# axiom_beta_plugin_module_TE0714_SATA_v0_.net
KiCad netlist of a schematic drawn in EAGLE
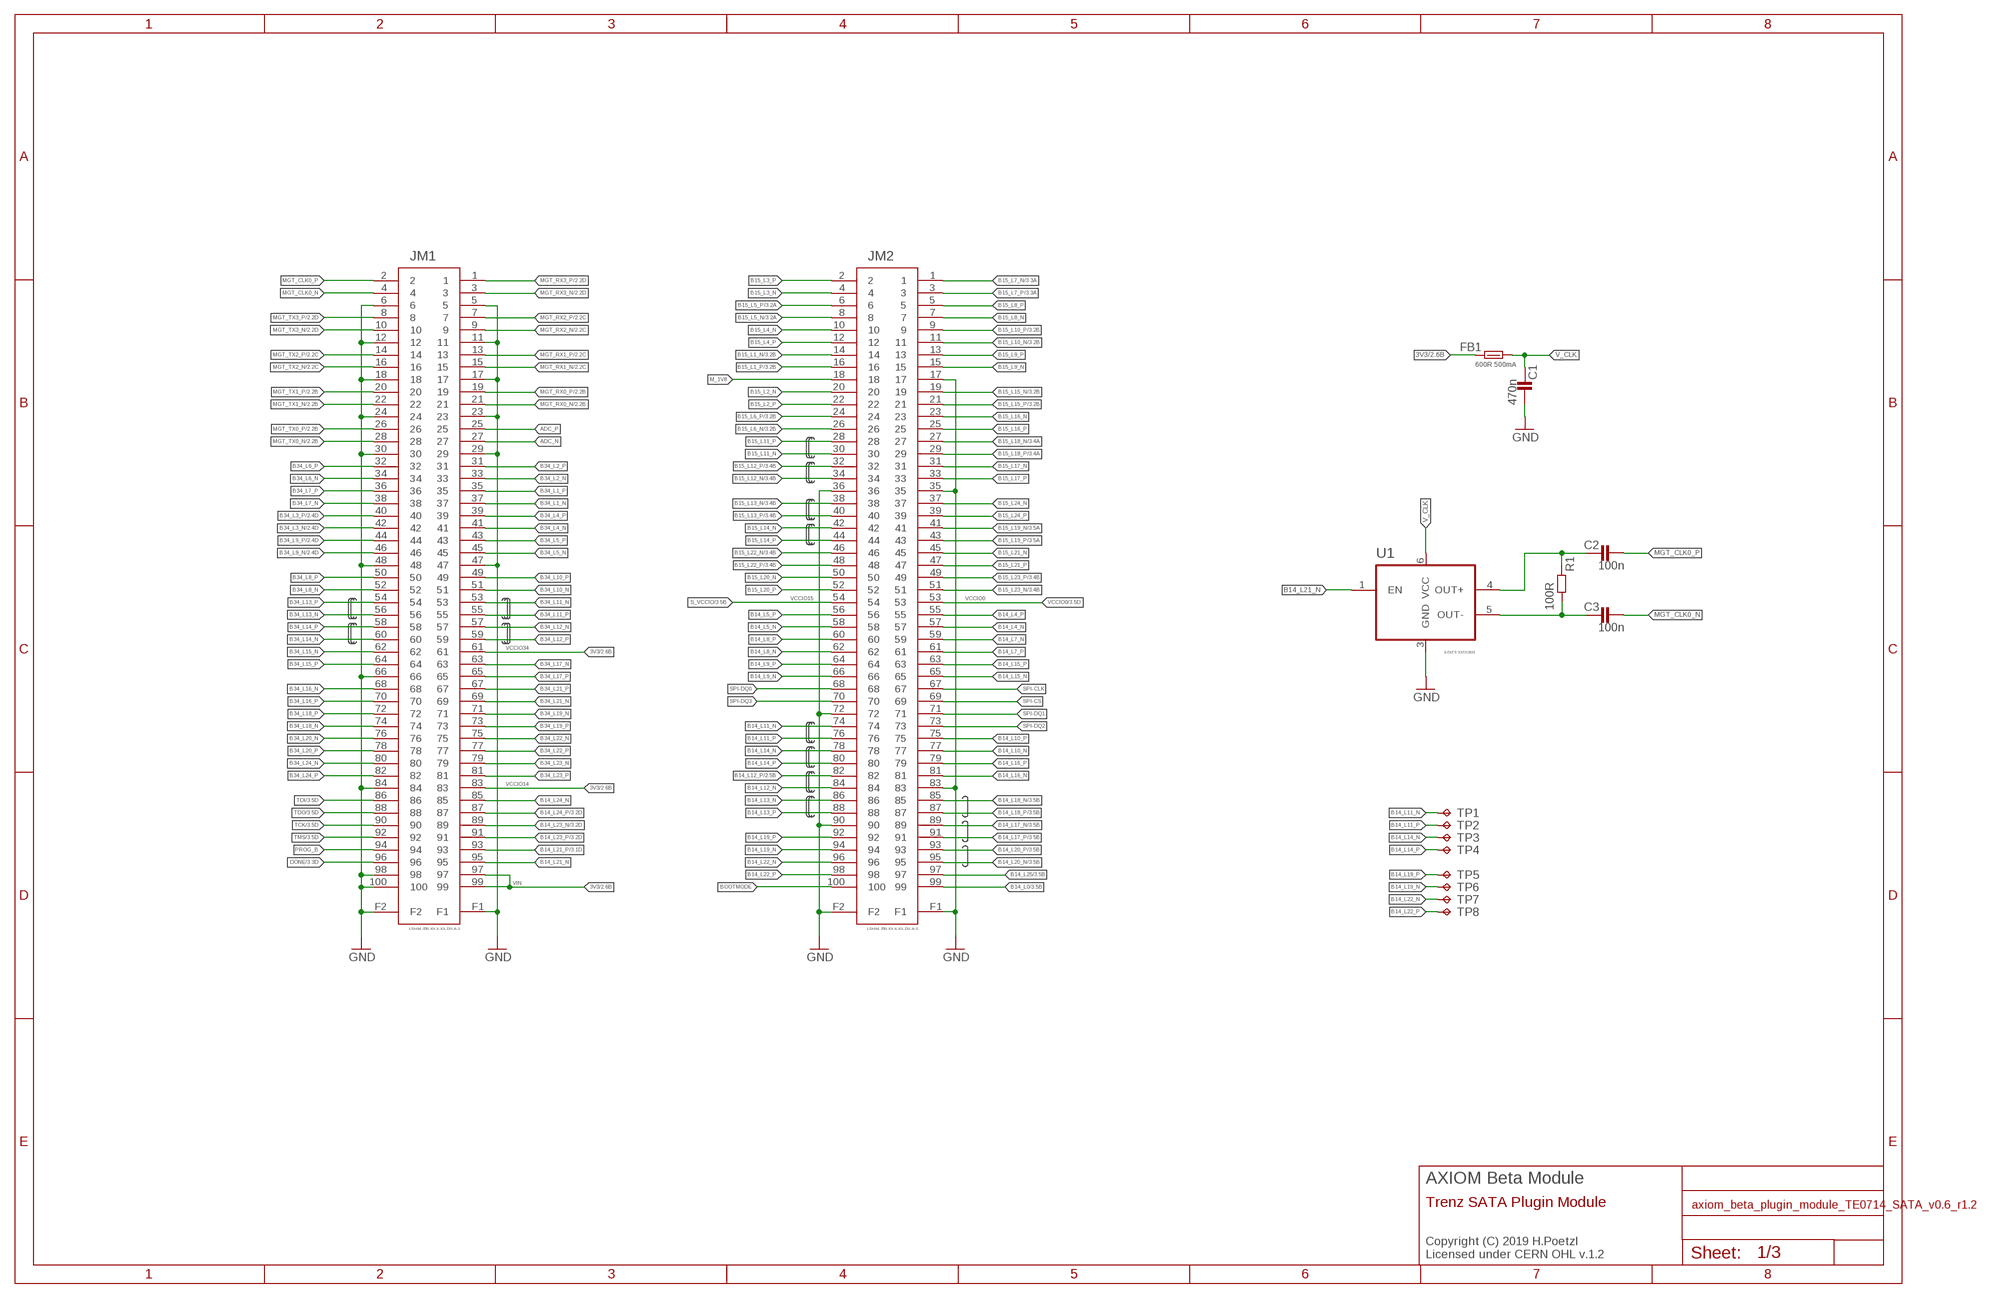
[diagram p0: schematic, sheet 1]
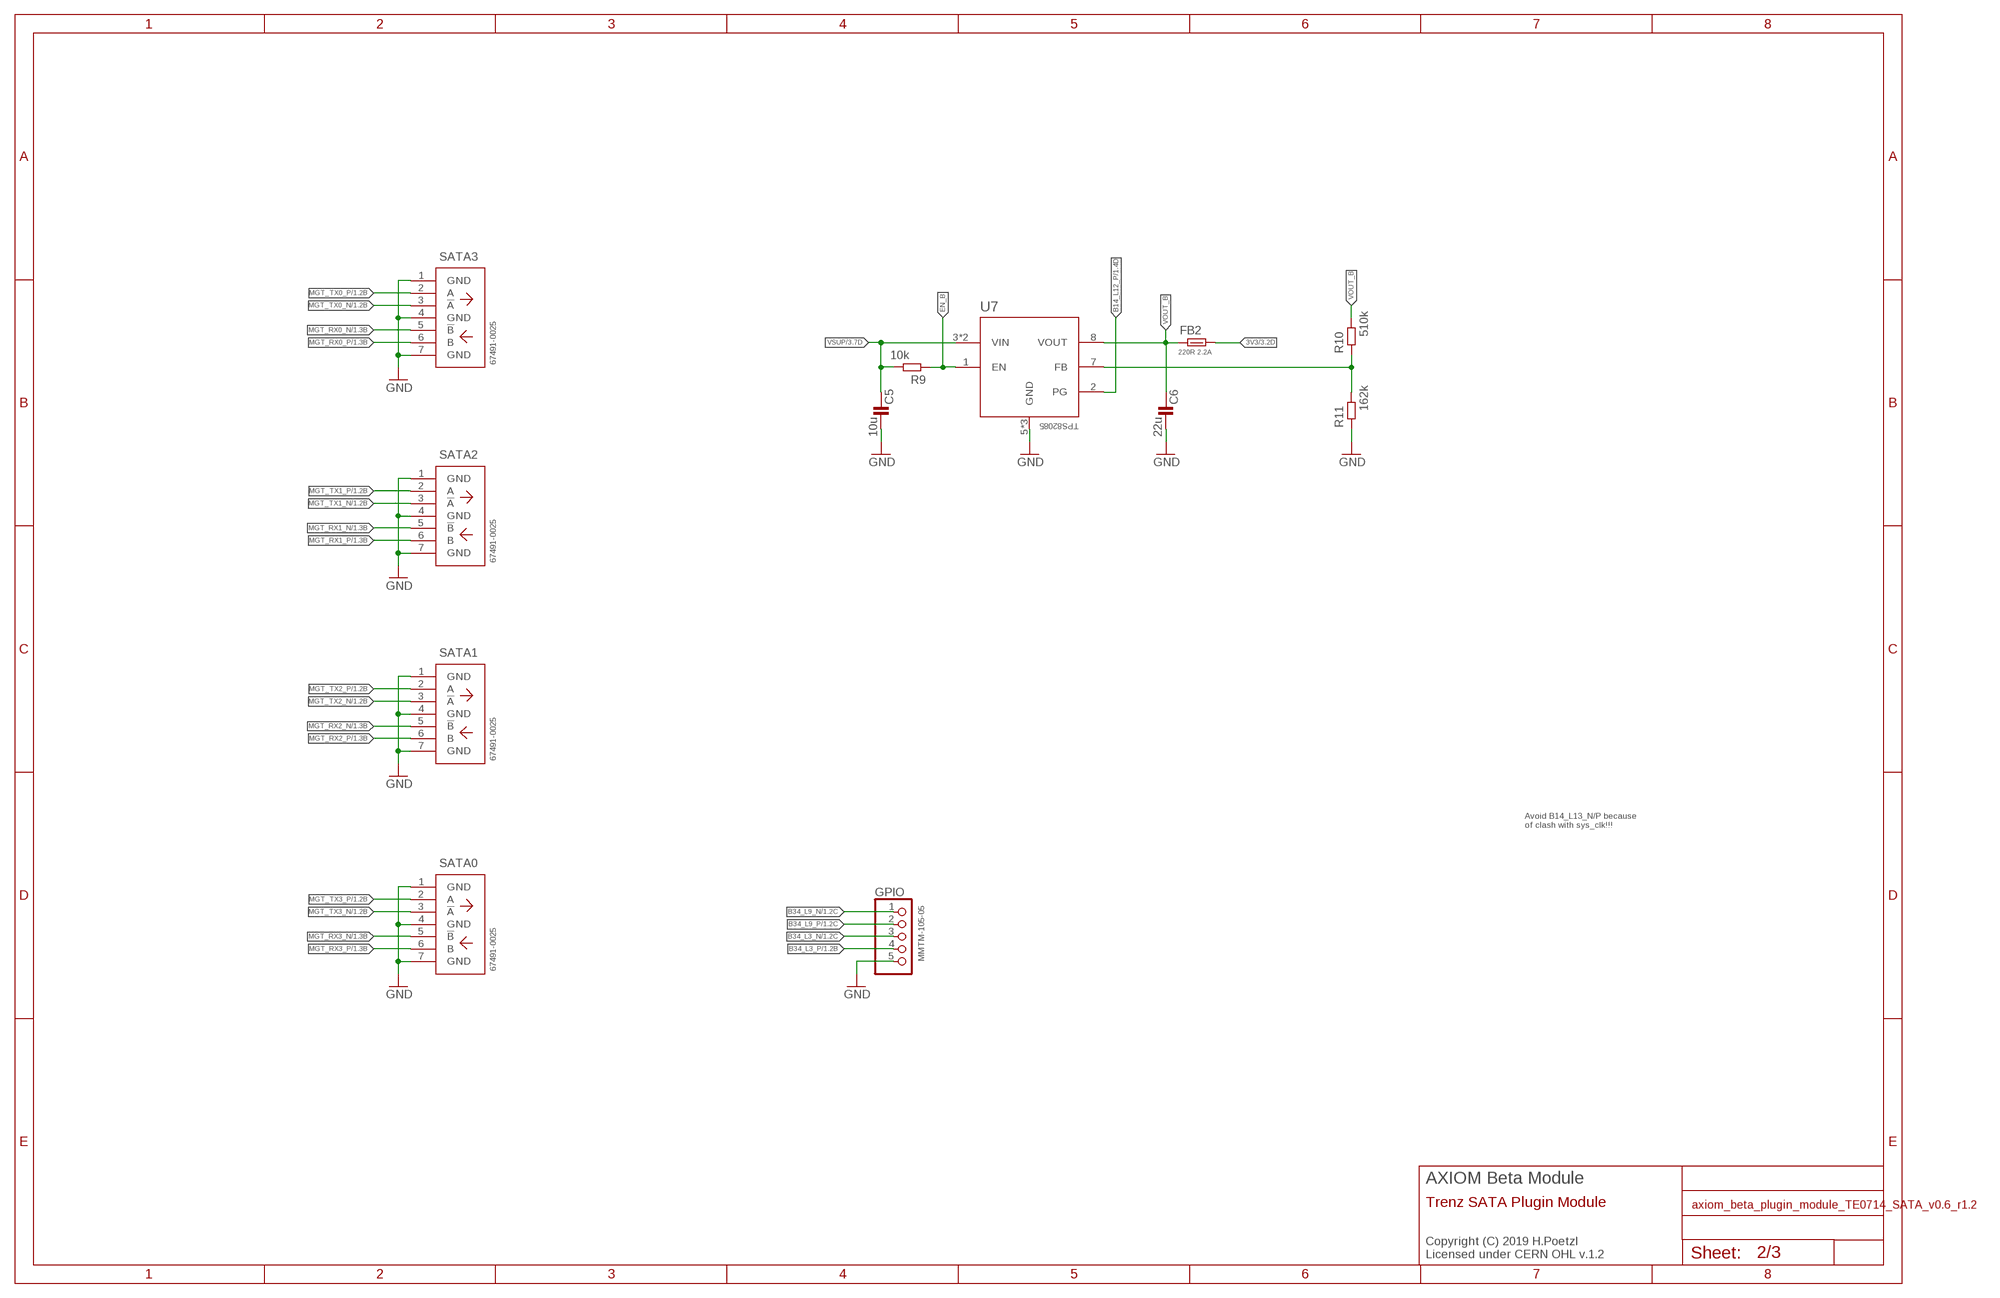
[diagram p1: schematic, sheet 2]
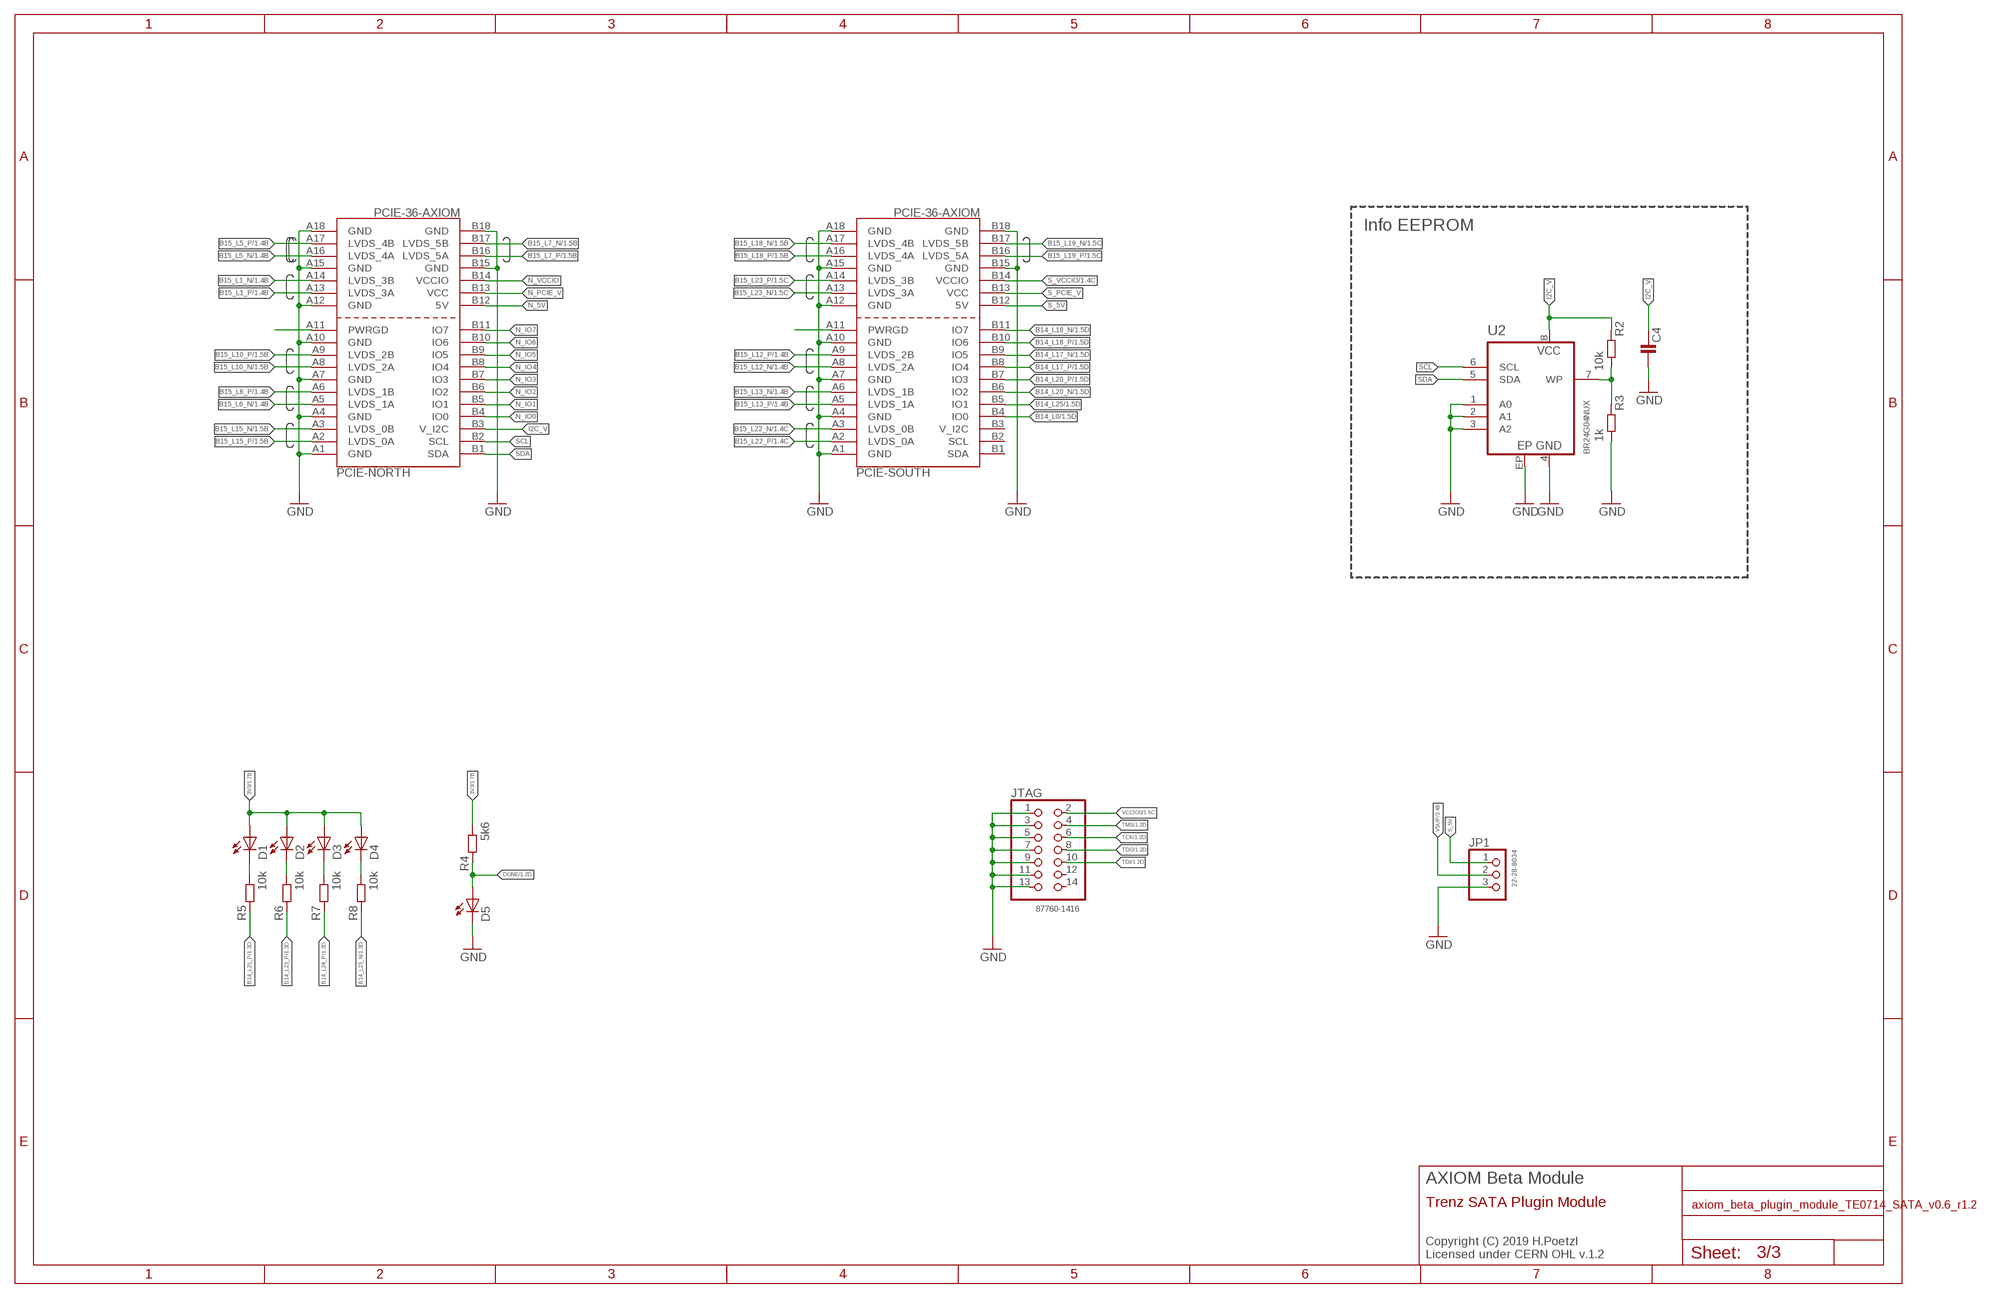
[diagram p2: schematic, sheet 3]

(export (version "E")
  (design (tool "Eeschema 10.0.6"))
  (components
    (comp (ref "C4")
      (value "C0402-B")
      (footprint "eagle-import:0402-B")
      (libsource (lib "eagle-import") (part "C0402-B"))
    )
    (comp (ref "D1")
      (value "LED")
      (footprint "eagle-import:CHIPLED_0603")
      (libsource (lib "eagle-import") (part "LED"))
    )
    (comp (ref "D2")
      (value "LED")
      (footprint "eagle-import:CHIPLED_0603")
      (libsource (lib "eagle-import") (part "LED"))
    )
    (comp (ref "D3")
      (value "LED")
      (footprint "eagle-import:CHIPLED_0603")
      (libsource (lib "eagle-import") (part "LED"))
    )
    (comp (ref "D4")
      (value "LED")
      (footprint "eagle-import:CHIPLED_0603")
      (libsource (lib "eagle-import") (part "LED"))
    )
    (comp (ref "D5")
      (value "LED")
      (footprint "eagle-import:CHIPLED_0603")
      (libsource (lib "eagle-import") (part "LED"))
    )
    (comp (ref "JP1")
      (value "22-28-8034")
      (footprint "eagle-import:1X03_90-S")
      (libsource (lib "eagle-import") (part "PINHD-1X03_2.54-90°-S"))
    )
    (comp (ref "JTAG")
      (value "87760-1416")
      (footprint "eagle-import:2X07M")
      (libsource (lib "eagle-import") (part "PINHD-2X07_2.00"))
    )
    (comp (ref "PCIE-NORTH")
      (value "PCIE-36-AXIOM")
      (footprint "eagle-import:PCIE-36-AXIOM")
      (libsource (lib "eagle-import") (part "PCIE-36-AXIOM"))
    )
    (comp (ref "PCIE-SOUTH")
      (value "PCIE-36-AXIOM")
      (footprint "eagle-import:PCIE-36-AXIOM")
      (libsource (lib "eagle-import") (part "PCIE-36-AXIOM"))
    )
    (comp (ref "R2")
      (value "10k")
      (footprint "eagle-import:0402-B")
      (libsource (lib "eagle-import") (part "R0402-B"))
    )
    (comp (ref "R3")
      (value "1k")
      (footprint "eagle-import:0402-B")
      (libsource (lib "eagle-import") (part "R0402-B"))
    )
    (comp (ref "R4")
      (value "5k6")
      (footprint "eagle-import:0402-C")
      (libsource (lib "eagle-import") (part "R0402-C"))
    )
    (comp (ref "R5")
      (value "10k")
      (footprint "eagle-import:0402-C")
      (libsource (lib "eagle-import") (part "R0402-C"))
    )
    (comp (ref "R6")
      (value "10k")
      (footprint "eagle-import:0402-C")
      (libsource (lib "eagle-import") (part "R0402-C"))
    )
    (comp (ref "R7")
      (value "10k")
      (footprint "eagle-import:0402-C")
      (libsource (lib "eagle-import") (part "R0402-C"))
    )
    (comp (ref "R8")
      (value "10k")
      (footprint "eagle-import:0402-C")
      (libsource (lib "eagle-import") (part "R0402-C"))
    )
    (comp (ref "U2")
      (value "BR24G04NUX")
      (footprint "eagle-import:DFN200X300X100-9N")
      (libsource (lib "eagle-import") (part "BR24G04NUX"))
    )
    (comp (ref "C5")
      (value "10u")
      (footprint "eagle-import:0603-C")
      (libsource (lib "eagle-import") (part "C0603-C"))
    )
    (comp (ref "C6")
      (value "22u")
      (footprint "eagle-import:0603-C")
      (libsource (lib "eagle-import") (part "C0603-C"))
    )
    (comp (ref "FB2")
      (value "220R 2.2A")
      (footprint "eagle-import:0603-C")
      (libsource (lib "eagle-import") (part "FB0603-C"))
    )
    (comp (ref "GPIO")
      (value "MMTM-105-05")
      (footprint "eagle-import:1X05M")
      (libsource (lib "eagle-import") (part "PINHD-1X05_2.00"))
    )
    (comp (ref "R9")
      (value "10k")
      (footprint "eagle-import:0201-C")
      (libsource (lib "eagle-import") (part "R0201-C"))
    )
    (comp (ref "R10")
      (value "510k")
      (footprint "eagle-import:0201-C")
      (libsource (lib "eagle-import") (part "R0201-C"))
    )
    (comp (ref "R11")
      (value "162k")
      (footprint "eagle-import:0201-C")
      (libsource (lib "eagle-import") (part "R0201-C"))
    )
    (comp (ref "SATA0")
      (value "67491-0025")
      (footprint "eagle-import:SATA7-VERT-S")
      (libsource (lib "eagle-import") (part "SATA7-VERT-S"))
    )
    (comp (ref "SATA1")
      (value "67491-0025")
      (footprint "eagle-import:SATA7-VERT-S")
      (libsource (lib "eagle-import") (part "SATA7-VERT-S"))
    )
    (comp (ref "SATA2")
      (value "67491-0025")
      (footprint "eagle-import:SATA7-VERT-S")
      (libsource (lib "eagle-import") (part "SATA7-VERT-S"))
    )
    (comp (ref "SATA3")
      (value "67491-0025")
      (footprint "eagle-import:SATA7-VERT-S")
      (libsource (lib "eagle-import") (part "SATA7-VERT-S"))
    )
    (comp (ref "U7")
      (value "TPS82085")
      (footprint "eagle-import:MICROSIP")
      (libsource (lib "eagle-import") (part "TPS82085"))
    )
    (comp (ref "C1")
      (value "470n")
      (footprint "eagle-import:0402-C")
      (libsource (lib "eagle-import") (part "C0402-C"))
    )
    (comp (ref "C2")
      (value "100n")
      (footprint "eagle-import:0201-C")
      (libsource (lib "eagle-import") (part "C0201-C"))
    )
    (comp (ref "C3")
      (value "100n")
      (footprint "eagle-import:0201-C")
      (libsource (lib "eagle-import") (part "C0201-C"))
    )
    (comp (ref "FB1")
      (value "600R 500mA")
      (footprint "eagle-import:0402-C")
      (libsource (lib "eagle-import") (part "FB0402-C"))
    )
    (comp (ref "JM1")
      (value "LSHM-150-XX.X-XX-DV-A-S")
      (footprint "eagle-import:LSHM-150-XX.X-XX-DV-A-S")
      (libsource (lib "eagle-import") (part "LSHM-150-XX.X-XX-DV-A-S"))
    )
    (comp (ref "JM2")
      (value "LSHM-150-XX.X-XX-DV-A-S")
      (footprint "eagle-import:LSHM-150-XX.X-XX-DV-A-S")
      (libsource (lib "eagle-import") (part "LSHM-150-XX.X-XX-DV-A-S"))
    )
    (comp (ref "R1")
      (value "100R")
      (footprint "eagle-import:0201-C")
      (libsource (lib "eagle-import") (part "R0201-C"))
    )
    (comp (ref "TP1")
      (value "TPTP10R")
      (footprint "eagle-import:TP10R")
      (libsource (lib "eagle-import") (part "TPTP10R"))
    )
    (comp (ref "TP2")
      (value "TPTP10R")
      (footprint "eagle-import:TP10R")
      (libsource (lib "eagle-import") (part "TPTP10R"))
    )
    (comp (ref "TP3")
      (value "TPTP10R")
      (footprint "eagle-import:TP10R")
      (libsource (lib "eagle-import") (part "TPTP10R"))
    )
    (comp (ref "TP4")
      (value "TPTP10R")
      (footprint "eagle-import:TP10R")
      (libsource (lib "eagle-import") (part "TPTP10R"))
    )
    (comp (ref "TP5")
      (value "TPTP10R")
      (footprint "eagle-import:TP10R")
      (libsource (lib "eagle-import") (part "TPTP10R"))
    )
    (comp (ref "TP6")
      (value "TPTP10R")
      (footprint "eagle-import:TP10R")
      (libsource (lib "eagle-import") (part "TPTP10R"))
    )
    (comp (ref "TP7")
      (value "TPTP10R")
      (footprint "eagle-import:TP10R")
      (libsource (lib "eagle-import") (part "TPTP10R"))
    )
    (comp (ref "TP8")
      (value "TPTP10R")
      (footprint "eagle-import:TP10R")
      (libsource (lib "eagle-import") (part "TPTP10R"))
    )
    (comp (ref "U1")
      (value "DSC11XX-3.2X2.5")
      (footprint "eagle-import:3.2X2.5")
      (libsource (lib "eagle-import") (part "DSC11XX-3.2X2.5"))
    )
  )
  (nets
    (net (code "1") (name "3V3") (class "Default")
      (node (ref "D1") (pin "A") (pinfunction "A_A") (pintype "passive"))
      (node (ref "D2") (pin "A") (pinfunction "A_A") (pintype "passive"))
      (node (ref "D3") (pin "A") (pinfunction "A_A") (pintype "passive"))
      (node (ref "D4") (pin "A") (pinfunction "A_A") (pintype "passive"))
      (node (ref "FB1") (pin "1") (pinfunction "1_1") (pintype "passive"))
      (node (ref "FB2") (pin "2") (pinfunction "2_2") (pintype "passive"))
      (node (ref "JM1") (pin "61") (pinfunction "61_61") (pintype "bidirectional"))
      (node (ref "JM1") (pin "83") (pinfunction "83_83") (pintype "bidirectional"))
      (node (ref "JM1") (pin "97") (pinfunction "97_97") (pintype "bidirectional"))
      (node (ref "JM1") (pin "99") (pinfunction "99_99") (pintype "bidirectional"))
      (node (ref "R4") (pin "2") (pinfunction "2_2") (pintype "passive"))
    )
    (net (code "2") (name "ADC_N") (class "Default")
      (node (ref "JM1") (pin "27") (pinfunction "27_27") (pintype "bidirectional"))
    )
    (net (code "3") (name "ADC_P") (class "Default")
      (node (ref "JM1") (pin "25") (pinfunction "25_25") (pintype "bidirectional"))
    )
    (net (code "4") (name "B14_L0") (class "Default")
      (node (ref "JM2") (pin "99") (pinfunction "99_99") (pintype "bidirectional"))
      (node (ref "PCIE-SOUTH") (pin "B4") (pinfunction "IO0_B4") (pintype "passive"))
    )
    (net (code "5") (name "B14_L4_N") (class "Default")
      (node (ref "JM2") (pin "57") (pinfunction "57_57") (pintype "bidirectional"))
    )
    (net (code "6") (name "B14_L4_P") (class "Default")
      (node (ref "JM2") (pin "55") (pinfunction "55_55") (pintype "bidirectional"))
    )
    (net (code "7") (name "B14_L5_N") (class "Default")
      (node (ref "JM2") (pin "58") (pinfunction "58_58") (pintype "bidirectional"))
    )
    (net (code "8") (name "B14_L5_P") (class "Default")
      (node (ref "JM2") (pin "56") (pinfunction "56_56") (pintype "bidirectional"))
    )
    (net (code "9") (name "B14_L7_N") (class "Default")
      (node (ref "JM2") (pin "59") (pinfunction "59_59") (pintype "bidirectional"))
    )
    (net (code "10") (name "B14_L7_P") (class "Default")
      (node (ref "JM2") (pin "61") (pinfunction "61_61") (pintype "bidirectional"))
    )
    (net (code "11") (name "B14_L8_N") (class "Default")
      (node (ref "JM2") (pin "62") (pinfunction "62_62") (pintype "bidirectional"))
    )
    (net (code "12") (name "B14_L8_P") (class "Default")
      (node (ref "JM2") (pin "60") (pinfunction "60_60") (pintype "bidirectional"))
    )
    (net (code "13") (name "B14_L9_N") (class "Default")
      (node (ref "JM2") (pin "66") (pinfunction "66_66") (pintype "bidirectional"))
    )
    (net (code "14") (name "B14_L9_P") (class "Default")
      (node (ref "JM2") (pin "64") (pinfunction "64_64") (pintype "bidirectional"))
    )
    (net (code "15") (name "B14_L10_N") (class "Default")
      (node (ref "JM2") (pin "77") (pinfunction "77_77") (pintype "bidirectional"))
    )
    (net (code "16") (name "B14_L10_P") (class "Default")
      (node (ref "JM2") (pin "75") (pinfunction "75_75") (pintype "bidirectional"))
    )
    (net (code "17") (name "B14_L11_N") (class "Default")
      (node (ref "JM2") (pin "74") (pinfunction "74_74") (pintype "bidirectional"))
      (node (ref "TP1") (pin "TP") (pinfunction "TP_TP") (pintype "input"))
    )
    (net (code "18") (name "B14_L11_P") (class "Default")
      (node (ref "JM2") (pin "76") (pinfunction "76_76") (pintype "bidirectional"))
      (node (ref "TP2") (pin "TP") (pinfunction "TP_TP") (pintype "input"))
    )
    (net (code "19") (name "B14_L12_N") (class "Default")
      (node (ref "JM2") (pin "84") (pinfunction "84_84") (pintype "bidirectional"))
    )
    (net (code "20") (name "B14_L12_P") (class "Default")
      (node (ref "JM2") (pin "82") (pinfunction "82_82") (pintype "bidirectional"))
      (node (ref "U7") (pin "2") (pinfunction "PG_2") (pintype "power_in"))
    )
    (net (code "21") (name "B14_L13_N") (class "Default")
      (node (ref "JM2") (pin "86") (pinfunction "86_86") (pintype "bidirectional"))
    )
    (net (code "22") (name "B14_L13_P") (class "Default")
      (node (ref "JM2") (pin "88") (pinfunction "88_88") (pintype "bidirectional"))
    )
    (net (code "23") (name "B14_L14_N") (class "Default")
      (node (ref "JM2") (pin "78") (pinfunction "78_78") (pintype "bidirectional"))
      (node (ref "TP3") (pin "TP") (pinfunction "TP_TP") (pintype "input"))
    )
    (net (code "24") (name "B14_L14_P") (class "Default")
      (node (ref "JM2") (pin "80") (pinfunction "80_80") (pintype "bidirectional"))
      (node (ref "TP4") (pin "TP") (pinfunction "TP_TP") (pintype "input"))
    )
    (net (code "25") (name "B14_L15_N") (class "Default")
      (node (ref "JM2") (pin "65") (pinfunction "65_65") (pintype "bidirectional"))
    )
    (net (code "26") (name "B14_L15_P") (class "Default")
      (node (ref "JM2") (pin "63") (pinfunction "63_63") (pintype "bidirectional"))
    )
    (net (code "27") (name "B14_L16_N") (class "Default")
      (node (ref "JM2") (pin "81") (pinfunction "81_81") (pintype "bidirectional"))
    )
    (net (code "28") (name "B14_L16_P") (class "Default")
      (node (ref "JM2") (pin "79") (pinfunction "79_79") (pintype "bidirectional"))
    )
    (net (code "29") (name "B14_L17_N") (class "Default")
      (node (ref "JM2") (pin "89") (pinfunction "89_89") (pintype "bidirectional"))
      (node (ref "PCIE-SOUTH") (pin "B9") (pinfunction "IO5_B9") (pintype "passive"))
    )
    (net (code "30") (name "B14_L17_P") (class "Default")
      (node (ref "JM2") (pin "91") (pinfunction "91_91") (pintype "bidirectional"))
      (node (ref "PCIE-SOUTH") (pin "B8") (pinfunction "IO4_B8") (pintype "passive"))
    )
    (net (code "31") (name "B14_L18_N") (class "Default")
      (node (ref "JM2") (pin "85") (pinfunction "85_85") (pintype "bidirectional"))
      (node (ref "PCIE-SOUTH") (pin "B11") (pinfunction "IO7_B11") (pintype "passive"))
    )
    (net (code "32") (name "B14_L18_P") (class "Default")
      (node (ref "JM2") (pin "87") (pinfunction "87_87") (pintype "bidirectional"))
      (node (ref "PCIE-SOUTH") (pin "B10") (pinfunction "IO6_B10") (pintype "passive"))
    )
    (net (code "33") (name "B14_L19_N") (class "Default")
      (node (ref "JM2") (pin "94") (pinfunction "94_94") (pintype "bidirectional"))
      (node (ref "TP6") (pin "TP") (pinfunction "TP_TP") (pintype "input"))
    )
    (net (code "34") (name "B14_L19_P") (class "Default")
      (node (ref "JM2") (pin "92") (pinfunction "92_92") (pintype "bidirectional"))
      (node (ref "TP5") (pin "TP") (pinfunction "TP_TP") (pintype "input"))
    )
    (net (code "35") (name "B14_L20_N") (class "Default")
      (node (ref "JM2") (pin "95") (pinfunction "95_95") (pintype "bidirectional"))
      (node (ref "PCIE-SOUTH") (pin "B6") (pinfunction "IO2_B6") (pintype "passive"))
    )
    (net (code "36") (name "B14_L20_P") (class "Default")
      (node (ref "JM2") (pin "93") (pinfunction "93_93") (pintype "bidirectional"))
      (node (ref "PCIE-SOUTH") (pin "B7") (pinfunction "IO3_B7") (pintype "passive"))
    )
    (net (code "37") (name "B14_L21_N") (class "Default")
      (node (ref "JM1") (pin "95") (pinfunction "95_95") (pintype "bidirectional"))
      (node (ref "U1") (pin "1") (pinfunction "EN_1") (pintype "input"))
    )
    (net (code "38") (name "B14_L21_P") (class "Default")
      (node (ref "JM1") (pin "93") (pinfunction "93_93") (pintype "bidirectional"))
      (node (ref "R5") (pin "1") (pinfunction "1_1") (pintype "passive"))
    )
    (net (code "39") (name "B14_L22_N") (class "Default")
      (node (ref "JM2") (pin "96") (pinfunction "96_96") (pintype "bidirectional"))
      (node (ref "TP7") (pin "TP") (pinfunction "TP_TP") (pintype "input"))
    )
    (net (code "40") (name "B14_L22_P") (class "Default")
      (node (ref "JM2") (pin "98") (pinfunction "98_98") (pintype "bidirectional"))
      (node (ref "TP8") (pin "TP") (pinfunction "TP_TP") (pintype "input"))
    )
    (net (code "41") (name "B14_L23_N") (class "Default")
      (node (ref "JM1") (pin "89") (pinfunction "89_89") (pintype "bidirectional"))
      (node (ref "R8") (pin "1") (pinfunction "1_1") (pintype "passive"))
    )
    (net (code "42") (name "B14_L23_P") (class "Default")
      (node (ref "JM1") (pin "91") (pinfunction "91_91") (pintype "bidirectional"))
      (node (ref "R6") (pin "1") (pinfunction "1_1") (pintype "passive"))
    )
    (net (code "43") (name "B14_L24_N") (class "Default")
      (node (ref "JM1") (pin "85") (pinfunction "85_85") (pintype "bidirectional"))
    )
    (net (code "44") (name "B14_L24_P") (class "Default")
      (node (ref "JM1") (pin "87") (pinfunction "87_87") (pintype "bidirectional"))
      (node (ref "R7") (pin "1") (pinfunction "1_1") (pintype "passive"))
    )
    (net (code "45") (name "B14_L25") (class "Default")
      (node (ref "JM2") (pin "97") (pinfunction "97_97") (pintype "bidirectional"))
      (node (ref "PCIE-SOUTH") (pin "B5") (pinfunction "IO1_B5") (pintype "passive"))
    )
    (net (code "46") (name "B15_L1_N") (class "Default")
      (node (ref "JM2") (pin "14") (pinfunction "14_14") (pintype "bidirectional"))
      (node (ref "PCIE-NORTH") (pin "A14") (pinfunction "LVDS_3B_A14") (pintype "passive"))
    )
    (net (code "47") (name "B15_L1_P") (class "Default")
      (node (ref "JM2") (pin "16") (pinfunction "16_16") (pintype "bidirectional"))
      (node (ref "PCIE-NORTH") (pin "A13") (pinfunction "LVDS_3A_A13") (pintype "passive"))
    )
    (net (code "48") (name "B15_L2_N") (class "Default")
      (node (ref "JM2") (pin "20") (pinfunction "20_20") (pintype "bidirectional"))
    )
    (net (code "49") (name "B15_L2_P") (class "Default")
      (node (ref "JM2") (pin "22") (pinfunction "22_22") (pintype "bidirectional"))
    )
    (net (code "50") (name "B15_L3_N") (class "Default")
      (node (ref "JM2") (pin "4") (pinfunction "4_4") (pintype "bidirectional"))
    )
    (net (code "51") (name "B15_L3_P") (class "Default")
      (node (ref "JM2") (pin "2") (pinfunction "2_2") (pintype "bidirectional"))
    )
    (net (code "52") (name "B15_L4_N") (class "Default")
      (node (ref "JM2") (pin "10") (pinfunction "10_10") (pintype "bidirectional"))
    )
    (net (code "53") (name "B15_L4_P") (class "Default")
      (node (ref "JM2") (pin "12") (pinfunction "12_12") (pintype "bidirectional"))
    )
    (net (code "54") (name "B15_L5_N") (class "Default")
      (node (ref "JM2") (pin "8") (pinfunction "8_8") (pintype "bidirectional"))
      (node (ref "PCIE-NORTH") (pin "A16") (pinfunction "LVDS_4A_A16") (pintype "passive"))
    )
    (net (code "55") (name "B15_L5_P") (class "Default")
      (node (ref "JM2") (pin "6") (pinfunction "6_6") (pintype "bidirectional"))
      (node (ref "PCIE-NORTH") (pin "A17") (pinfunction "LVDS_4B_A17") (pintype "passive"))
    )
    (net (code "56") (name "B15_L6_N") (class "Default")
      (node (ref "JM2") (pin "26") (pinfunction "26_26") (pintype "bidirectional"))
      (node (ref "PCIE-NORTH") (pin "A5") (pinfunction "LVDS_1A_A5") (pintype "passive"))
    )
    (net (code "57") (name "B15_L6_P") (class "Default")
      (node (ref "JM2") (pin "24") (pinfunction "24_24") (pintype "bidirectional"))
      (node (ref "PCIE-NORTH") (pin "A6") (pinfunction "LVDS_1B_A6") (pintype "passive"))
    )
    (net (code "58") (name "B15_L7_N") (class "Default")
      (node (ref "JM2") (pin "1") (pinfunction "1_1") (pintype "bidirectional"))
      (node (ref "PCIE-NORTH") (pin "B17") (pinfunction "LVDS_5B_B17") (pintype "passive"))
    )
    (net (code "59") (name "B15_L7_P") (class "Default")
      (node (ref "JM2") (pin "3") (pinfunction "3_3") (pintype "bidirectional"))
      (node (ref "PCIE-NORTH") (pin "B16") (pinfunction "LVDS_5A_B16") (pintype "passive"))
    )
    (net (code "60") (name "B15_L8_N") (class "Default")
      (node (ref "JM2") (pin "7") (pinfunction "7_7") (pintype "bidirectional"))
    )
    (net (code "61") (name "B15_L8_P") (class "Default")
      (node (ref "JM2") (pin "5") (pinfunction "5_5") (pintype "bidirectional"))
    )
    (net (code "62") (name "B15_L9_N") (class "Default")
      (node (ref "JM2") (pin "15") (pinfunction "15_15") (pintype "bidirectional"))
    )
    (net (code "63") (name "B15_L9_P") (class "Default")
      (node (ref "JM2") (pin "13") (pinfunction "13_13") (pintype "bidirectional"))
    )
    (net (code "64") (name "B15_L10_N") (class "Default")
      (node (ref "JM2") (pin "11") (pinfunction "11_11") (pintype "bidirectional"))
      (node (ref "PCIE-NORTH") (pin "A8") (pinfunction "LVDS_2A_A8") (pintype "passive"))
    )
    (net (code "65") (name "B15_L10_P") (class "Default")
      (node (ref "JM2") (pin "9") (pinfunction "9_9") (pintype "bidirectional"))
      (node (ref "PCIE-NORTH") (pin "A9") (pinfunction "LVDS_2B_A9") (pintype "passive"))
    )
    (net (code "66") (name "B15_L11_N") (class "Default")
      (node (ref "JM2") (pin "30") (pinfunction "30_30") (pintype "bidirectional"))
    )
    (net (code "67") (name "B15_L11_P") (class "Default")
      (node (ref "JM2") (pin "28") (pinfunction "28_28") (pintype "bidirectional"))
    )
    (net (code "68") (name "B15_L12_N") (class "Default")
      (node (ref "JM2") (pin "34") (pinfunction "34_34") (pintype "bidirectional"))
      (node (ref "PCIE-SOUTH") (pin "A8") (pinfunction "LVDS_2A_A8") (pintype "passive"))
    )
    (net (code "69") (name "B15_L12_P") (class "Default")
      (node (ref "JM2") (pin "32") (pinfunction "32_32") (pintype "bidirectional"))
      (node (ref "PCIE-SOUTH") (pin "A9") (pinfunction "LVDS_2B_A9") (pintype "passive"))
    )
    (net (code "70") (name "B15_L13_N") (class "Default")
      (node (ref "JM2") (pin "38") (pinfunction "38_38") (pintype "bidirectional"))
      (node (ref "PCIE-SOUTH") (pin "A6") (pinfunction "LVDS_1B_A6") (pintype "passive"))
    )
    (net (code "71") (name "B15_L13_P") (class "Default")
      (node (ref "JM2") (pin "40") (pinfunction "40_40") (pintype "bidirectional"))
      (node (ref "PCIE-SOUTH") (pin "A5") (pinfunction "LVDS_1A_A5") (pintype "passive"))
    )
    (net (code "72") (name "B15_L14_N") (class "Default")
      (node (ref "JM2") (pin "42") (pinfunction "42_42") (pintype "bidirectional"))
    )
    (net (code "73") (name "B15_L14_P") (class "Default")
      (node (ref "JM2") (pin "44") (pinfunction "44_44") (pintype "bidirectional"))
    )
    (net (code "74") (name "B15_L15_N") (class "Default")
      (node (ref "JM2") (pin "19") (pinfunction "19_19") (pintype "bidirectional"))
      (node (ref "PCIE-NORTH") (pin "A3") (pinfunction "LVDS_0B_A3") (pintype "passive"))
    )
    (net (code "75") (name "B15_L15_P") (class "Default")
      (node (ref "JM2") (pin "21") (pinfunction "21_21") (pintype "bidirectional"))
      (node (ref "PCIE-NORTH") (pin "A2") (pinfunction "LVDS_0A_A2") (pintype "passive"))
    )
    (net (code "76") (name "B15_L16_N") (class "Default")
      (node (ref "JM2") (pin "23") (pinfunction "23_23") (pintype "bidirectional"))
    )
    (net (code "77") (name "B15_L16_P") (class "Default")
      (node (ref "JM2") (pin "25") (pinfunction "25_25") (pintype "bidirectional"))
    )
    (net (code "78") (name "B15_L17_N") (class "Default")
      (node (ref "JM2") (pin "31") (pinfunction "31_31") (pintype "bidirectional"))
    )
    (net (code "79") (name "B15_L17_P") (class "Default")
      (node (ref "JM2") (pin "33") (pinfunction "33_33") (pintype "bidirectional"))
    )
    (net (code "80") (name "B15_L18_N") (class "Default")
      (node (ref "JM2") (pin "27") (pinfunction "27_27") (pintype "bidirectional"))
      (node (ref "PCIE-SOUTH") (pin "A17") (pinfunction "LVDS_4B_A17") (pintype "passive"))
    )
    (net (code "81") (name "B15_L18_P") (class "Default")
      (node (ref "JM2") (pin "29") (pinfunction "29_29") (pintype "bidirectional"))
      (node (ref "PCIE-SOUTH") (pin "A16") (pinfunction "LVDS_4A_A16") (pintype "passive"))
    )
    (net (code "82") (name "B15_L19_N") (class "Default")
      (node (ref "JM2") (pin "41") (pinfunction "41_41") (pintype "bidirectional"))
      (node (ref "PCIE-SOUTH") (pin "B17") (pinfunction "LVDS_5B_B17") (pintype "passive"))
    )
    (net (code "83") (name "B15_L19_P") (class "Default")
      (node (ref "JM2") (pin "43") (pinfunction "43_43") (pintype "bidirectional"))
      (node (ref "PCIE-SOUTH") (pin "B16") (pinfunction "LVDS_5A_B16") (pintype "passive"))
    )
    (net (code "84") (name "B15_L20_N") (class "Default")
      (node (ref "JM2") (pin "50") (pinfunction "50_50") (pintype "bidirectional"))
    )
    (net (code "85") (name "B15_L20_P") (class "Default")
      (node (ref "JM2") (pin "52") (pinfunction "52_52") (pintype "bidirectional"))
    )
    (net (code "86") (name "B15_L21_N") (class "Default")
      (node (ref "JM2") (pin "45") (pinfunction "45_45") (pintype "bidirectional"))
    )
    (net (code "87") (name "B15_L21_P") (class "Default")
      (node (ref "JM2") (pin "47") (pinfunction "47_47") (pintype "bidirectional"))
    )
    (net (code "88") (name "B15_L22_N") (class "Default")
      (node (ref "JM2") (pin "46") (pinfunction "46_46") (pintype "bidirectional"))
      (node (ref "PCIE-SOUTH") (pin "A3") (pinfunction "LVDS_0B_A3") (pintype "passive"))
    )
    (net (code "89") (name "B15_L22_P") (class "Default")
      (node (ref "JM2") (pin "48") (pinfunction "48_48") (pintype "bidirectional"))
      (node (ref "PCIE-SOUTH") (pin "A2") (pinfunction "LVDS_0A_A2") (pintype "passive"))
    )
    (net (code "90") (name "B15_L23_N") (class "Default")
      (node (ref "JM2") (pin "51") (pinfunction "51_51") (pintype "bidirectional"))
      (node (ref "PCIE-SOUTH") (pin "A13") (pinfunction "LVDS_3A_A13") (pintype "passive"))
    )
    (net (code "91") (name "B15_L23_P") (class "Default")
      (node (ref "JM2") (pin "49") (pinfunction "49_49") (pintype "bidirectional"))
      (node (ref "PCIE-SOUTH") (pin "A14") (pinfunction "LVDS_3B_A14") (pintype "passive"))
    )
    (net (code "92") (name "B15_L24_N") (class "Default")
      (node (ref "JM2") (pin "37") (pinfunction "37_37") (pintype "bidirectional"))
    )
    (net (code "93") (name "B15_L24_P") (class "Default")
      (node (ref "JM2") (pin "39") (pinfunction "39_39") (pintype "bidirectional"))
    )
    (net (code "94") (name "B34_L1_N") (class "Default")
      (node (ref "JM1") (pin "37") (pinfunction "37_37") (pintype "bidirectional"))
    )
    (net (code "95") (name "B34_L1_P") (class "Default")
      (node (ref "JM1") (pin "35") (pinfunction "35_35") (pintype "bidirectional"))
    )
    (net (code "96") (name "B34_L2_N") (class "Default")
      (node (ref "JM1") (pin "33") (pinfunction "33_33") (pintype "bidirectional"))
    )
    (net (code "97") (name "B34_L2_P") (class "Default")
      (node (ref "JM1") (pin "31") (pinfunction "31_31") (pintype "bidirectional"))
    )
    (net (code "98") (name "B34_L3_N") (class "Default")
      (node (ref "GPIO") (pin "3") (pinfunction "3_3") (pintype "passive"))
      (node (ref "JM1") (pin "42") (pinfunction "42_42") (pintype "bidirectional"))
    )
    (net (code "99") (name "B34_L3_P") (class "Default")
      (node (ref "GPIO") (pin "4") (pinfunction "4_4") (pintype "passive"))
      (node (ref "JM1") (pin "40") (pinfunction "40_40") (pintype "bidirectional"))
    )
    (net (code "100") (name "B34_L4_N") (class "Default")
      (node (ref "JM1") (pin "41") (pinfunction "41_41") (pintype "bidirectional"))
    )
    (net (code "101") (name "B34_L4_P") (class "Default")
      (node (ref "JM1") (pin "39") (pinfunction "39_39") (pintype "bidirectional"))
    )
    (net (code "102") (name "B34_L5_N") (class "Default")
      (node (ref "JM1") (pin "45") (pinfunction "45_45") (pintype "bidirectional"))
    )
    (net (code "103") (name "B34_L5_P") (class "Default")
      (node (ref "JM1") (pin "43") (pinfunction "43_43") (pintype "bidirectional"))
    )
    (net (code "104") (name "B34_L6_N") (class "Default")
      (node (ref "JM1") (pin "34") (pinfunction "34_34") (pintype "bidirectional"))
    )
    (net (code "105") (name "B34_L6_P") (class "Default")
      (node (ref "JM1") (pin "32") (pinfunction "32_32") (pintype "bidirectional"))
    )
    (net (code "106") (name "B34_L7_N") (class "Default")
      (node (ref "JM1") (pin "38") (pinfunction "38_38") (pintype "bidirectional"))
    )
    (net (code "107") (name "B34_L7_P") (class "Default")
      (node (ref "JM1") (pin "36") (pinfunction "36_36") (pintype "bidirectional"))
    )
    (net (code "108") (name "B34_L8_N") (class "Default")
      (node (ref "JM1") (pin "52") (pinfunction "52_52") (pintype "bidirectional"))
    )
    (net (code "109") (name "B34_L8_P") (class "Default")
      (node (ref "JM1") (pin "50") (pinfunction "50_50") (pintype "bidirectional"))
    )
    (net (code "110") (name "B34_L9_N") (class "Default")
      (node (ref "GPIO") (pin "1") (pinfunction "1_1") (pintype "passive"))
      (node (ref "JM1") (pin "46") (pinfunction "46_46") (pintype "bidirectional"))
    )
    (net (code "111") (name "B34_L9_P") (class "Default")
      (node (ref "GPIO") (pin "2") (pinfunction "2_2") (pintype "passive"))
      (node (ref "JM1") (pin "44") (pinfunction "44_44") (pintype "bidirectional"))
    )
    (net (code "112") (name "B34_L10_N") (class "Default")
      (node (ref "JM1") (pin "51") (pinfunction "51_51") (pintype "bidirectional"))
    )
    (net (code "113") (name "B34_L10_P") (class "Default")
      (node (ref "JM1") (pin "49") (pinfunction "49_49") (pintype "bidirectional"))
    )
    (net (code "114") (name "B34_L11_N") (class "Default")
      (node (ref "JM1") (pin "53") (pinfunction "53_53") (pintype "bidirectional"))
    )
    (net (code "115") (name "B34_L11_P") (class "Default")
      (node (ref "JM1") (pin "55") (pinfunction "55_55") (pintype "bidirectional"))
    )
    (net (code "116") (name "B34_L12_N") (class "Default")
      (node (ref "JM1") (pin "57") (pinfunction "57_57") (pintype "bidirectional"))
    )
    (net (code "117") (name "B34_L12_P") (class "Default")
      (node (ref "JM1") (pin "59") (pinfunction "59_59") (pintype "bidirectional"))
    )
    (net (code "118") (name "B34_L13_N") (class "Default")
      (node (ref "JM1") (pin "56") (pinfunction "56_56") (pintype "bidirectional"))
    )
    (net (code "119") (name "B34_L13_P") (class "Default")
      (node (ref "JM1") (pin "54") (pinfunction "54_54") (pintype "bidirectional"))
    )
    (net (code "120") (name "B34_L14_N") (class "Default")
      (node (ref "JM1") (pin "60") (pinfunction "60_60") (pintype "bidirectional"))
    )
    (net (code "121") (name "B34_L14_P") (class "Default")
      (node (ref "JM1") (pin "58") (pinfunction "58_58") (pintype "bidirectional"))
    )
    (net (code "122") (name "B34_L15_N") (class "Default")
      (node (ref "JM1") (pin "62") (pinfunction "62_62") (pintype "bidirectional"))
    )
    (net (code "123") (name "B34_L15_P") (class "Default")
      (node (ref "JM1") (pin "64") (pinfunction "64_64") (pintype "bidirectional"))
    )
    (net (code "124") (name "B34_L16_N") (class "Default")
      (node (ref "JM1") (pin "68") (pinfunction "68_68") (pintype "bidirectional"))
    )
    (net (code "125") (name "B34_L16_P") (class "Default")
      (node (ref "JM1") (pin "70") (pinfunction "70_70") (pintype "bidirectional"))
    )
    (net (code "126") (name "B34_L17_N") (class "Default")
      (node (ref "JM1") (pin "63") (pinfunction "63_63") (pintype "bidirectional"))
    )
    (net (code "127") (name "B34_L17_P") (class "Default")
      (node (ref "JM1") (pin "65") (pinfunction "65_65") (pintype "bidirectional"))
    )
    (net (code "128") (name "B34_L18_N") (class "Default")
      (node (ref "JM1") (pin "74") (pinfunction "74_74") (pintype "bidirectional"))
    )
    (net (code "129") (name "B34_L18_P") (class "Default")
      (node (ref "JM1") (pin "72") (pinfunction "72_72") (pintype "bidirectional"))
    )
    (net (code "130") (name "B34_L19_N") (class "Default")
      (node (ref "JM1") (pin "71") (pinfunction "71_71") (pintype "bidirectional"))
    )
    (net (code "131") (name "B34_L19_P") (class "Default")
      (node (ref "JM1") (pin "73") (pinfunction "73_73") (pintype "bidirectional"))
    )
    (net (code "132") (name "B34_L20_N") (class "Default")
      (node (ref "JM1") (pin "76") (pinfunction "76_76") (pintype "bidirectional"))
    )
    (net (code "133") (name "B34_L20_P") (class "Default")
      (node (ref "JM1") (pin "78") (pinfunction "78_78") (pintype "bidirectional"))
    )
    (net (code "134") (name "B34_L21_N") (class "Default")
      (node (ref "JM1") (pin "69") (pinfunction "69_69") (pintype "bidirectional"))
    )
    (net (code "135") (name "B34_L21_P") (class "Default")
      (node (ref "JM1") (pin "67") (pinfunction "67_67") (pintype "bidirectional"))
    )
    (net (code "136") (name "B34_L22_N") (class "Default")
      (node (ref "JM1") (pin "75") (pinfunction "75_75") (pintype "bidirectional"))
    )
    (net (code "137") (name "B34_L22_P") (class "Default")
      (node (ref "JM1") (pin "77") (pinfunction "77_77") (pintype "bidirectional"))
    )
    (net (code "138") (name "B34_L23_N") (class "Default")
      (node (ref "JM1") (pin "79") (pinfunction "79_79") (pintype "bidirectional"))
    )
    (net (code "139") (name "B34_L23_P") (class "Default")
      (node (ref "JM1") (pin "81") (pinfunction "81_81") (pintype "bidirectional"))
    )
    (net (code "140") (name "B34_L24_N") (class "Default")
      (node (ref "JM1") (pin "80") (pinfunction "80_80") (pintype "bidirectional"))
    )
    (net (code "141") (name "B34_L24_P") (class "Default")
      (node (ref "JM1") (pin "82") (pinfunction "82_82") (pintype "bidirectional"))
    )
    (net (code "142") (name "BOOTMODE") (class "Default")
      (node (ref "JM2") (pin "100") (pinfunction "100_100") (pintype "bidirectional"))
    )
    (net (code "143") (name "DONE") (class "Default")
      (node (ref "D5") (pin "A") (pinfunction "A_A") (pintype "passive"))
      (node (ref "JM1") (pin "96") (pinfunction "96_96") (pintype "bidirectional"))
      (node (ref "R4") (pin "1") (pinfunction "1_1") (pintype "passive"))
    )
    (net (code "144") (name "EN_B") (class "Default")
      (node (ref "R9") (pin "1") (pinfunction "1_1") (pintype "passive"))
      (node (ref "U7") (pin "1") (pinfunction "EN_1") (pintype "input"))
    )
    (net (code "145") (name "GND") (class "Default")
      (node (ref "C1") (pin "2") (pinfunction "2_2") (pintype "passive"))
      (node (ref "C4") (pin "2") (pinfunction "2_2") (pintype "passive"))
      (node (ref "C5") (pin "2") (pinfunction "2_2") (pintype "passive"))
      (node (ref "C6") (pin "2") (pinfunction "2_2") (pintype "passive"))
      (node (ref "D5") (pin "C") (pinfunction "C_C") (pintype "passive"))
      (node (ref "GPIO") (pin "5") (pinfunction "5_5") (pintype "passive"))
      (node (ref "JM1") (pin "100") (pinfunction "100_100") (pintype "bidirectional"))
      (node (ref "JM1") (pin "11") (pinfunction "11_11") (pintype "bidirectional"))
      (node (ref "JM1") (pin "12") (pinfunction "12_12") (pintype "bidirectional"))
      (node (ref "JM1") (pin "17") (pinfunction "17_17") (pintype "bidirectional"))
      (node (ref "JM1") (pin "18") (pinfunction "18_18") (pintype "bidirectional"))
      (node (ref "JM1") (pin "23") (pinfunction "23_23") (pintype "bidirectional"))
      (node (ref "JM1") (pin "24") (pinfunction "24_24") (pintype "bidirectional"))
      (node (ref "JM1") (pin "29") (pinfunction "29_29") (pintype "bidirectional"))
      (node (ref "JM1") (pin "30") (pinfunction "30_30") (pintype "bidirectional"))
      (node (ref "JM1") (pin "47") (pinfunction "47_47") (pintype "bidirectional"))
      (node (ref "JM1") (pin "48") (pinfunction "48_48") (pintype "bidirectional"))
      (node (ref "JM1") (pin "5") (pinfunction "5_5") (pintype "bidirectional"))
      (node (ref "JM1") (pin "6") (pinfunction "6_6") (pintype "bidirectional"))
      (node (ref "JM1") (pin "66") (pinfunction "66_66") (pintype "bidirectional"))
      (node (ref "JM1") (pin "84") (pinfunction "84_84") (pintype "bidirectional"))
      (node (ref "JM1") (pin "98") (pinfunction "98_98") (pintype "bidirectional"))
      (node (ref "JM1") (pin "F1") (pinfunction "F1_F1") (pintype "bidirectional"))
      (node (ref "JM1") (pin "F2") (pinfunction "F2_F2") (pintype "bidirectional"))
      (node (ref "JM2") (pin "17") (pinfunction "17_17") (pintype "bidirectional"))
      (node (ref "JM2") (pin "35") (pinfunction "35_35") (pintype "bidirectional"))
      (node (ref "JM2") (pin "36") (pinfunction "36_36") (pintype "bidirectional"))
      (node (ref "JM2") (pin "72") (pinfunction "72_72") (pintype "bidirectional"))
      (node (ref "JM2") (pin "83") (pinfunction "83_83") (pintype "bidirectional"))
      (node (ref "JM2") (pin "90") (pinfunction "90_90") (pintype "bidirectional"))
      (node (ref "JM2") (pin "F1") (pinfunction "F1_F1") (pintype "bidirectional"))
      (node (ref "JM2") (pin "F2") (pinfunction "F2_F2") (pintype "bidirectional"))
      (node (ref "JP1") (pin "3") (pinfunction "3_3") (pintype "passive"))
      (node (ref "JTAG") (pin "1") (pinfunction "1_1") (pintype "passive"))
      (node (ref "JTAG") (pin "11") (pinfunction "11_11") (pintype "passive"))
      (node (ref "JTAG") (pin "13") (pinfunction "13_13") (pintype "passive"))
      (node (ref "JTAG") (pin "3") (pinfunction "3_3") (pintype "passive"))
      (node (ref "JTAG") (pin "5") (pinfunction "5_5") (pintype "passive"))
      (node (ref "JTAG") (pin "7") (pinfunction "7_7") (pintype "passive"))
      (node (ref "JTAG") (pin "9") (pinfunction "9_9") (pintype "passive"))
      (node (ref "PCIE-NORTH") (pin "A1") (pinfunction "GND_A1") (pintype "passive"))
      (node (ref "PCIE-NORTH") (pin "A10") (pinfunction "GND_A10") (pintype "passive"))
      (node (ref "PCIE-NORTH") (pin "A12") (pinfunction "GND_A12") (pintype "passive"))
      (node (ref "PCIE-NORTH") (pin "A15") (pinfunction "GND_A15") (pintype "passive"))
      (node (ref "PCIE-NORTH") (pin "A18") (pinfunction "GND_A18") (pintype "passive"))
      (node (ref "PCIE-NORTH") (pin "A4") (pinfunction "GND_A4") (pintype "passive"))
      (node (ref "PCIE-NORTH") (pin "A7") (pinfunction "GND_A7") (pintype "passive"))
      (node (ref "PCIE-NORTH") (pin "B15") (pinfunction "GND_B15") (pintype "passive"))
      (node (ref "PCIE-NORTH") (pin "B18") (pinfunction "GND_B18") (pintype "passive"))
      (node (ref "PCIE-SOUTH") (pin "A1") (pinfunction "GND_A1") (pintype "passive"))
      (node (ref "PCIE-SOUTH") (pin "A10") (pinfunction "GND_A10") (pintype "passive"))
      (node (ref "PCIE-SOUTH") (pin "A12") (pinfunction "GND_A12") (pintype "passive"))
      (node (ref "PCIE-SOUTH") (pin "A15") (pinfunction "GND_A15") (pintype "passive"))
      (node (ref "PCIE-SOUTH") (pin "A18") (pinfunction "GND_A18") (pintype "passive"))
      (node (ref "PCIE-SOUTH") (pin "A4") (pinfunction "GND_A4") (pintype "passive"))
      (node (ref "PCIE-SOUTH") (pin "A7") (pinfunction "GND_A7") (pintype "passive"))
      (node (ref "PCIE-SOUTH") (pin "B15") (pinfunction "GND_B15") (pintype "passive"))
      (node (ref "PCIE-SOUTH") (pin "B18") (pinfunction "GND_B18") (pintype "passive"))
      (node (ref "R11") (pin "1") (pinfunction "1_1") (pintype "passive"))
      (node (ref "R3") (pin "2") (pinfunction "2_2") (pintype "passive"))
      (node (ref "SATA0") (pin "1") (pinfunction "GND_1") (pintype "power_in"))
      (node (ref "SATA0") (pin "4") (pinfunction "GND_4") (pintype "power_in"))
      (node (ref "SATA0") (pin "7") (pinfunction "GND_7") (pintype "power_in"))
      (node (ref "SATA1") (pin "1") (pinfunction "GND_1") (pintype "power_in"))
      (node (ref "SATA1") (pin "4") (pinfunction "GND_4") (pintype "power_in"))
      (node (ref "SATA1") (pin "7") (pinfunction "GND_7") (pintype "power_in"))
      (node (ref "SATA2") (pin "1") (pinfunction "GND_1") (pintype "power_in"))
      (node (ref "SATA2") (pin "4") (pinfunction "GND_4") (pintype "power_in"))
      (node (ref "SATA2") (pin "7") (pinfunction "GND_7") (pintype "power_in"))
      (node (ref "SATA3") (pin "1") (pinfunction "GND_1") (pintype "power_in"))
      (node (ref "SATA3") (pin "4") (pinfunction "GND_4") (pintype "power_in"))
      (node (ref "SATA3") (pin "7") (pinfunction "GND_7") (pintype "power_in"))
      (node (ref "U1") (pin "3") (pinfunction "GND_3") (pintype "passive"))
      (node (ref "U2") (pin "1") (pinfunction "A0_1") (pintype "input"))
      (node (ref "U2") (pin "2") (pinfunction "A1_2") (pintype "input"))
      (node (ref "U2") (pin "3") (pinfunction "A2_3") (pintype "input"))
      (node (ref "U2") (pin "4") (pinfunction "GND_4") (pintype "passive"))
      (node (ref "U2") (pin "EP") (pinfunction "EP_EP") (pintype "passive"))
      (node (ref "U7") (pin "5") (pinfunction "GND_5") (pintype "passive"))
      (node (ref "U7") (pin "6") (pinfunction "GND_6") (pintype "passive"))
      (node (ref "U7") (pin "EP") (pinfunction "GND_EP") (pintype "passive"))
    )
    (net (code "146") (name "I2C_V") (class "Default")
      (node (ref "C4") (pin "1") (pinfunction "1_1") (pintype "passive"))
      (node (ref "PCIE-NORTH") (pin "B3") (pinfunction "V_I2C_B3") (pintype "passive"))
      (node (ref "R2") (pin "1") (pinfunction "1_1") (pintype "passive"))
      (node (ref "U2") (pin "8") (pinfunction "VCC_8") (pintype "power_in"))
    )
    (net (code "147") (name "MGT_CLK0_N") (class "Default")
      (node (ref "C3") (pin "2") (pinfunction "2_2") (pintype "passive"))
      (node (ref "JM1") (pin "4") (pinfunction "4_4") (pintype "bidirectional"))
    )
    (net (code "148") (name "MGT_CLK0_P") (class "Default")
      (node (ref "C2") (pin "2") (pinfunction "2_2") (pintype "passive"))
      (node (ref "JM1") (pin "2") (pinfunction "2_2") (pintype "bidirectional"))
    )
    (net (code "149") (name "MGT_RX0_N") (class "Default")
      (node (ref "JM1") (pin "21") (pinfunction "21_21") (pintype "bidirectional"))
      (node (ref "SATA3") (pin "5") (pinfunction "~{B}_5") (pintype "bidirectional"))
    )
    (net (code "150") (name "MGT_RX0_P") (class "Default")
      (node (ref "JM1") (pin "19") (pinfunction "19_19") (pintype "bidirectional"))
      (node (ref "SATA3") (pin "6") (pinfunction "B_6") (pintype "bidirectional"))
    )
    (net (code "151") (name "MGT_RX1_N") (class "Default")
      (node (ref "JM1") (pin "15") (pinfunction "15_15") (pintype "bidirectional"))
      (node (ref "SATA2") (pin "5") (pinfunction "~{B}_5") (pintype "bidirectional"))
    )
    (net (code "152") (name "MGT_RX1_P") (class "Default")
      (node (ref "JM1") (pin "13") (pinfunction "13_13") (pintype "bidirectional"))
      (node (ref "SATA2") (pin "6") (pinfunction "B_6") (pintype "bidirectional"))
    )
    (net (code "153") (name "MGT_RX2_N") (class "Default")
      (node (ref "JM1") (pin "9") (pinfunction "9_9") (pintype "bidirectional"))
      (node (ref "SATA1") (pin "5") (pinfunction "~{B}_5") (pintype "bidirectional"))
    )
    (net (code "154") (name "MGT_RX2_P") (class "Default")
      (node (ref "JM1") (pin "7") (pinfunction "7_7") (pintype "bidirectional"))
      (node (ref "SATA1") (pin "6") (pinfunction "B_6") (pintype "bidirectional"))
    )
    (net (code "155") (name "MGT_RX3_N") (class "Default")
      (node (ref "JM1") (pin "3") (pinfunction "3_3") (pintype "bidirectional"))
      (node (ref "SATA0") (pin "5") (pinfunction "~{B}_5") (pintype "bidirectional"))
    )
    (net (code "156") (name "MGT_RX3_P") (class "Default")
      (node (ref "JM1") (pin "1") (pinfunction "1_1") (pintype "bidirectional"))
      (node (ref "SATA0") (pin "6") (pinfunction "B_6") (pintype "bidirectional"))
    )
    (net (code "157") (name "MGT_TX0_N") (class "Default")
      (node (ref "JM1") (pin "28") (pinfunction "28_28") (pintype "bidirectional"))
      (node (ref "SATA3") (pin "3") (pinfunction "~{A}_3") (pintype "bidirectional"))
    )
    (net (code "158") (name "MGT_TX0_P") (class "Default")
      (node (ref "JM1") (pin "26") (pinfunction "26_26") (pintype "bidirectional"))
      (node (ref "SATA3") (pin "2") (pinfunction "A_2") (pintype "bidirectional"))
    )
    (net (code "159") (name "MGT_TX1_N") (class "Default")
      (node (ref "JM1") (pin "22") (pinfunction "22_22") (pintype "bidirectional"))
      (node (ref "SATA2") (pin "3") (pinfunction "~{A}_3") (pintype "bidirectional"))
    )
    (net (code "160") (name "MGT_TX1_P") (class "Default")
      (node (ref "JM1") (pin "20") (pinfunction "20_20") (pintype "bidirectional"))
      (node (ref "SATA2") (pin "2") (pinfunction "A_2") (pintype "bidirectional"))
    )
    (net (code "161") (name "MGT_TX2_N") (class "Default")
      (node (ref "JM1") (pin "16") (pinfunction "16_16") (pintype "bidirectional"))
      (node (ref "SATA1") (pin "3") (pinfunction "~{A}_3") (pintype "bidirectional"))
    )
    (net (code "162") (name "MGT_TX2_P") (class "Default")
      (node (ref "JM1") (pin "14") (pinfunction "14_14") (pintype "bidirectional"))
      (node (ref "SATA1") (pin "2") (pinfunction "A_2") (pintype "bidirectional"))
    )
    (net (code "163") (name "MGT_TX3_N") (class "Default")
      (node (ref "JM1") (pin "10") (pinfunction "10_10") (pintype "bidirectional"))
      (node (ref "SATA0") (pin "3") (pinfunction "~{A}_3") (pintype "bidirectional"))
    )
    (net (code "164") (name "MGT_TX3_P") (class "Default")
      (node (ref "JM1") (pin "8") (pinfunction "8_8") (pintype "bidirectional"))
      (node (ref "SATA0") (pin "2") (pinfunction "A_2") (pintype "bidirectional"))
    )
    (net (code "165") (name "M_1V8") (class "Default")
      (node (ref "JM2") (pin "18") (pinfunction "18_18") (pintype "bidirectional"))
    )
    (net (code "166") (name "N_5V") (class "Default")
      (node (ref "PCIE-NORTH") (pin "B12") (pinfunction "5V_B12") (pintype "passive"))
    )
    (net (code "167") (name "N_IO0") (class "Default")
      (node (ref "PCIE-NORTH") (pin "B4") (pinfunction "IO0_B4") (pintype "passive"))
    )
    (net (code "168") (name "N_IO1") (class "Default")
      (node (ref "PCIE-NORTH") (pin "B5") (pinfunction "IO1_B5") (pintype "passive"))
    )
    (net (code "169") (name "N_IO2") (class "Default")
      (node (ref "PCIE-NORTH") (pin "B6") (pinfunction "IO2_B6") (pintype "passive"))
    )
    (net (code "170") (name "N_IO3") (class "Default")
      (node (ref "PCIE-NORTH") (pin "B7") (pinfunction "IO3_B7") (pintype "passive"))
    )
    (net (code "171") (name "N_IO4") (class "Default")
      (node (ref "PCIE-NORTH") (pin "B8") (pinfunction "IO4_B8") (pintype "passive"))
    )
    (net (code "172") (name "N_IO5") (class "Default")
      (node (ref "PCIE-NORTH") (pin "B9") (pinfunction "IO5_B9") (pintype "passive"))
    )
    (net (code "173") (name "N_IO6") (class "Default")
      (node (ref "PCIE-NORTH") (pin "B10") (pinfunction "IO6_B10") (pintype "passive"))
    )
    (net (code "174") (name "N_IO7") (class "Default")
      (node (ref "PCIE-NORTH") (pin "B11") (pinfunction "IO7_B11") (pintype "passive"))
    )
    (net (code "175") (name "N_PCIE_V") (class "Default")
      (node (ref "PCIE-NORTH") (pin "B13") (pinfunction "VCC_B13") (pintype "passive"))
    )
    (net (code "176") (name "N_VCCIO") (class "Default")
      (node (ref "PCIE-NORTH") (pin "B14") (pinfunction "VCCIO_B14") (pintype "passive"))
    )
    (net (code "177") (name "Net-(D1-PadC)") (class "Default")
      (node (ref "D1") (pin "C") (pinfunction "C_C") (pintype "passive"))
      (node (ref "R5") (pin "2") (pinfunction "2_2") (pintype "passive"))
    )
    (net (code "178") (name "Net-(D2-PadC)") (class "Default")
      (node (ref "D2") (pin "C") (pinfunction "C_C") (pintype "passive"))
      (node (ref "R6") (pin "2") (pinfunction "2_2") (pintype "passive"))
    )
    (net (code "179") (name "Net-(D3-PadC)") (class "Default")
      (node (ref "D3") (pin "C") (pinfunction "C_C") (pintype "passive"))
      (node (ref "R7") (pin "2") (pinfunction "2_2") (pintype "passive"))
    )
    (net (code "180") (name "Net-(D4-PadC)") (class "Default")
      (node (ref "D4") (pin "C") (pinfunction "C_C") (pintype "passive"))
      (node (ref "R8") (pin "2") (pinfunction "2_2") (pintype "passive"))
    )
    (net (code "181") (name "Net-(U1-OUT+)") (class "Default")
      (node (ref "C2") (pin "1") (pinfunction "1_1") (pintype "passive"))
      (node (ref "R1") (pin "1") (pinfunction "1_1") (pintype "passive"))
      (node (ref "U1") (pin "4") (pinfunction "OUT+_4") (pintype "output"))
    )
    (net (code "182") (name "Net-(U1-OUT-)") (class "Default")
      (node (ref "C3") (pin "1") (pinfunction "1_1") (pintype "passive"))
      (node (ref "R1") (pin "2") (pinfunction "2_2") (pintype "passive"))
      (node (ref "U1") (pin "5") (pinfunction "OUT-_5") (pintype "output"))
    )
    (net (code "183") (name "Net-(U2-WP)") (class "Default")
      (node (ref "R2") (pin "2") (pinfunction "2_2") (pintype "passive"))
      (node (ref "R3") (pin "1") (pinfunction "1_1") (pintype "passive"))
      (node (ref "U2") (pin "7") (pinfunction "WP_7") (pintype "input"))
    )
    (net (code "184") (name "Net-(U7-FB)") (class "Default")
      (node (ref "R10") (pin "1") (pinfunction "1_1") (pintype "passive"))
      (node (ref "R11") (pin "2") (pinfunction "2_2") (pintype "passive"))
      (node (ref "U7") (pin "7") (pinfunction "FB_7") (pintype "output"))
    )
    (net (code "185") (name "PROG_B") (class "Default")
      (node (ref "JM1") (pin "94") (pinfunction "94_94") (pintype "bidirectional"))
    )
    (net (code "186") (name "SCL") (class "Default")
      (node (ref "PCIE-NORTH") (pin "B2") (pinfunction "SCL_B2") (pintype "passive"))
      (node (ref "U2") (pin "6") (pinfunction "SCL_6") (pintype "input"))
    )
    (net (code "187") (name "SDA") (class "Default")
      (node (ref "PCIE-NORTH") (pin "B1") (pinfunction "SDA_B1") (pintype "passive"))
      (node (ref "U2") (pin "5") (pinfunction "SDA_5") (pintype "bidirectional"))
    )
    (net (code "188") (name "SPI-CLK") (class "Default")
      (node (ref "JM2") (pin "67") (pinfunction "67_67") (pintype "bidirectional"))
    )
    (net (code "189") (name "SPI-CS") (class "Default")
      (node (ref "JM2") (pin "69") (pinfunction "69_69") (pintype "bidirectional"))
    )
    (net (code "190") (name "SPI-DQ0") (class "Default")
      (node (ref "JM2") (pin "68") (pinfunction "68_68") (pintype "bidirectional"))
    )
    (net (code "191") (name "SPI-DQ1") (class "Default")
      (node (ref "JM2") (pin "71") (pinfunction "71_71") (pintype "bidirectional"))
    )
    (net (code "192") (name "SPI-DQ2") (class "Default")
      (node (ref "JM2") (pin "73") (pinfunction "73_73") (pintype "bidirectional"))
    )
    (net (code "193") (name "SPI-DQ3") (class "Default")
      (node (ref "JM2") (pin "70") (pinfunction "70_70") (pintype "bidirectional"))
    )
    (net (code "194") (name "S_5V") (class "Default")
      (node (ref "JP1") (pin "1") (pinfunction "1_1") (pintype "passive"))
      (node (ref "PCIE-SOUTH") (pin "B12") (pinfunction "5V_B12") (pintype "passive"))
    )
    (net (code "195") (name "S_PCIE_V") (class "Default")
      (node (ref "PCIE-SOUTH") (pin "B13") (pinfunction "VCC_B13") (pintype "passive"))
    )
    (net (code "196") (name "S_VCCIO") (class "Default")
      (node (ref "JM2") (pin "54") (pinfunction "54_54") (pintype "bidirectional"))
      (node (ref "PCIE-SOUTH") (pin "B14") (pinfunction "VCCIO_B14") (pintype "passive"))
    )
    (net (code "197") (name "TCK") (class "Default")
      (node (ref "JM1") (pin "90") (pinfunction "90_90") (pintype "bidirectional"))
      (node (ref "JTAG") (pin "6") (pinfunction "6_6") (pintype "passive"))
    )
    (net (code "198") (name "TDI") (class "Default")
      (node (ref "JM1") (pin "86") (pinfunction "86_86") (pintype "bidirectional"))
      (node (ref "JTAG") (pin "10") (pinfunction "10_10") (pintype "passive"))
    )
    (net (code "199") (name "TDO") (class "Default")
      (node (ref "JM1") (pin "88") (pinfunction "88_88") (pintype "bidirectional"))
      (node (ref "JTAG") (pin "8") (pinfunction "8_8") (pintype "passive"))
    )
    (net (code "200") (name "TMS") (class "Default")
      (node (ref "JM1") (pin "92") (pinfunction "92_92") (pintype "bidirectional"))
      (node (ref "JTAG") (pin "4") (pinfunction "4_4") (pintype "passive"))
    )
    (net (code "201") (name "VCCIO0") (class "Default")
      (node (ref "JM2") (pin "53") (pinfunction "53_53") (pintype "bidirectional"))
      (node (ref "JTAG") (pin "2") (pinfunction "2_2") (pintype "passive"))
    )
    (net (code "202") (name "VOUT_B") (class "Default")
      (node (ref "C6") (pin "1") (pinfunction "1_1") (pintype "passive"))
      (node (ref "FB2") (pin "1") (pinfunction "1_1") (pintype "passive"))
      (node (ref "R10") (pin "2") (pinfunction "2_2") (pintype "passive"))
      (node (ref "U7") (pin "8") (pinfunction "VOUT_8") (pintype "output"))
    )
    (net (code "203") (name "VSUP") (class "Default")
      (node (ref "C5") (pin "1") (pinfunction "1_1") (pintype "passive"))
      (node (ref "JP1") (pin "2") (pinfunction "2_2") (pintype "passive"))
      (node (ref "R9") (pin "2") (pinfunction "2_2") (pintype "passive"))
      (node (ref "U7") (pin "3") (pinfunction "VIN_3") (pintype "power_in"))
      (node (ref "U7") (pin "4") (pinfunction "VIN_4") (pintype "power_in"))
    )
    (net (code "204") (name "V_CLK") (class "Default")
      (node (ref "C1") (pin "1") (pinfunction "1_1") (pintype "passive"))
      (node (ref "FB1") (pin "2") (pinfunction "2_2") (pintype "passive"))
      (node (ref "U1") (pin "6") (pinfunction "VCC_6") (pintype "power_in"))
    )
    (net (code "205") (name "unconnected-(JTAG-Pad12)") (class "Default")
      (node (ref "JTAG") (pin "12") (pinfunction "12_12") (pintype "passive"))
    )
    (net (code "206") (name "unconnected-(JTAG-Pad14)") (class "Default")
      (node (ref "JTAG") (pin "14") (pinfunction "14_14") (pintype "passive"))
    )
    (net (code "207") (name "unconnected-(PCIE-NORTH-PWRGD-PadA11)") (class "Default")
      (node (ref "PCIE-NORTH") (pin "A11") (pinfunction "PWRGD_A11") (pintype "passive"))
    )
    (net (code "208") (name "unconnected-(PCIE-SOUTH-PWRGD-PadA11)") (class "Default")
      (node (ref "PCIE-SOUTH") (pin "A11") (pinfunction "PWRGD_A11") (pintype "passive"))
    )
    (net (code "209") (name "unconnected-(PCIE-SOUTH-SCL-PadB2)") (class "Default")
      (node (ref "PCIE-SOUTH") (pin "B2") (pinfunction "SCL_B2") (pintype "passive"))
    )
    (net (code "210") (name "unconnected-(PCIE-SOUTH-SDA-PadB1)") (class "Default")
      (node (ref "PCIE-SOUTH") (pin "B1") (pinfunction "SDA_B1") (pintype "passive"))
    )
    (net (code "211") (name "unconnected-(PCIE-SOUTH-V_I2C-PadB3)") (class "Default")
      (node (ref "PCIE-SOUTH") (pin "B3") (pinfunction "V_I2C_B3") (pintype "passive"))
    )
  )
)
